# TMP75C.net
KiCad netlist of a schematic drawn in Altium Designer
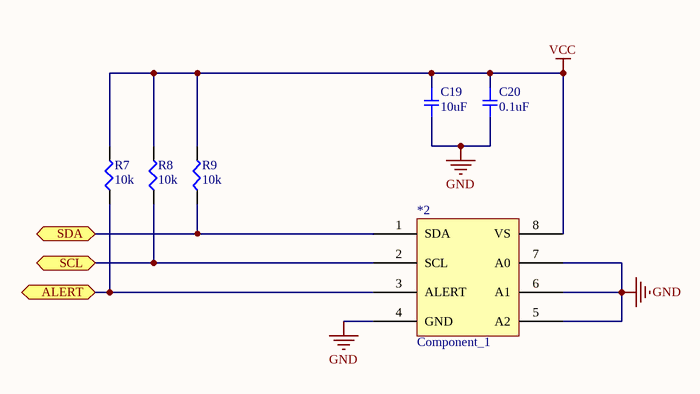
[diagram p0: TMP75C.SchDoc]

(export (version "E")
  (design (tool "Eeschema 10.0.6"))
  (components
    (comp (ref "*2")
      (value "Component_1")
      (footprint "TMP75C")
      (libsource (lib "TMP75C") (part "Component_1"))
    )
    (comp (ref "C19")
      (value "10uF")
      (footprint "SMD-0805C")
      (description "Cap Ceramic 10uF 25V X5R 10% 0805")
      (fields
        (field (name "PART NUMBER") "CL21A106KAFN3NE")
        (field (name "MANUFACTURER") "Samsung Electro-Mechanics")
      )
      (libsource (lib "capacitor_0805") (part "CL21A106KAFN3NE"))
    )
    (comp (ref "C20")
      (value "0.1uF")
      (footprint "SMD-0805C")
      (description "CAP CER 0.1uF 50V X7T 0805")
      (fields
        (field (name "PART NUMBER") "GC321AD72E103KX01D")
        (field (name "MANUFACTURER") "Samsung Electro-Mechanics")
      )
      (libsource (lib "capacitor_0805") (part "CL21B104JBCNNNC"))
    )
    (comp (ref "R7")
      (value "10k")
      (footprint "SMD-0805-RES")
      (description "RES SMD 10K OHM 5% 1/2W 0805")
      (fields (field (name "PART NUMBER") "ERJ-P6WJ103V") (field (name "DIGI-KEY PART NUMBER") "P16966CT-ND"))
      (libsource (lib "Panasonic_ERJ_0805") (part "ERJ-P6WJ103V"))
    )
    (comp (ref "R8")
      (value "10k")
      (footprint "SMD-0805-RES")
      (description "RES SMD 10K OHM 5% 1/2W 0805")
      (fields (field (name "PART NUMBER") "ERJ-P6WJ103V") (field (name "DIGI-KEY PART NUMBER") "P16966CT-ND"))
      (libsource (lib "Panasonic_ERJ_0805") (part "ERJ-P6WJ103V"))
    )
    (comp (ref "R9")
      (value "10k")
      (footprint "SMD-0805-RES")
      (description "RES SMD 10K OHM 5% 1/2W 0805")
      (fields (field (name "PART NUMBER") "ERJ-P6WJ103V") (field (name "DIGI-KEY PART NUMBER") "P16966CT-ND"))
      (libsource (lib "Panasonic_ERJ_0805") (part "ERJ-P6WJ103V"))
    )
  )
  (nets
    (net (code "1") (name "/ALERT") (class "Default")
      (node (ref "*2") (pin "3") (pinfunction "ALERT_3") (pintype "passive"))
      (node (ref "R7") (pin "1") (pinfunction "1_1") (pintype "passive"))
    )
    (net (code "2") (name "/SCL") (class "Default")
      (node (ref "*2") (pin "2") (pinfunction "SCL_2") (pintype "passive"))
      (node (ref "R8") (pin "1") (pinfunction "1_1") (pintype "passive"))
    )
    (net (code "3") (name "/SDA") (class "Default")
      (node (ref "*2") (pin "1") (pinfunction "SDA_1") (pintype "passive"))
      (node (ref "R9") (pin "1") (pinfunction "1_1") (pintype "passive"))
    )
    (net (code "4") (name "GND") (class "Default")
      (node (ref "*2") (pin "4") (pinfunction "GND_4") (pintype "passive"))
      (node (ref "*2") (pin "5") (pinfunction "A2_5") (pintype "passive"))
      (node (ref "*2") (pin "6") (pinfunction "A1_6") (pintype "passive"))
      (node (ref "*2") (pin "7") (pinfunction "A0_7") (pintype "passive"))
      (node (ref "C19") (pin "2") (pinfunction "2_2") (pintype "passive"))
      (node (ref "C20") (pin "2") (pinfunction "2_2") (pintype "passive"))
    )
    (net (code "5") (name "VCC") (class "Default")
      (node (ref "*2") (pin "8") (pinfunction "VS_8") (pintype "passive"))
      (node (ref "C19") (pin "1") (pinfunction "1_1") (pintype "passive"))
      (node (ref "C20") (pin "1") (pinfunction "1_1") (pintype "passive"))
      (node (ref "R7") (pin "2") (pinfunction "2_2") (pintype "passive"))
      (node (ref "R8") (pin "2") (pinfunction "2_2") (pintype "passive"))
      (node (ref "R9") (pin "2") (pinfunction "2_2") (pintype "passive"))
    )
  )
)
